# Mux_Demux.net
KiCad netlist of a schematic drawn in Altium Designer
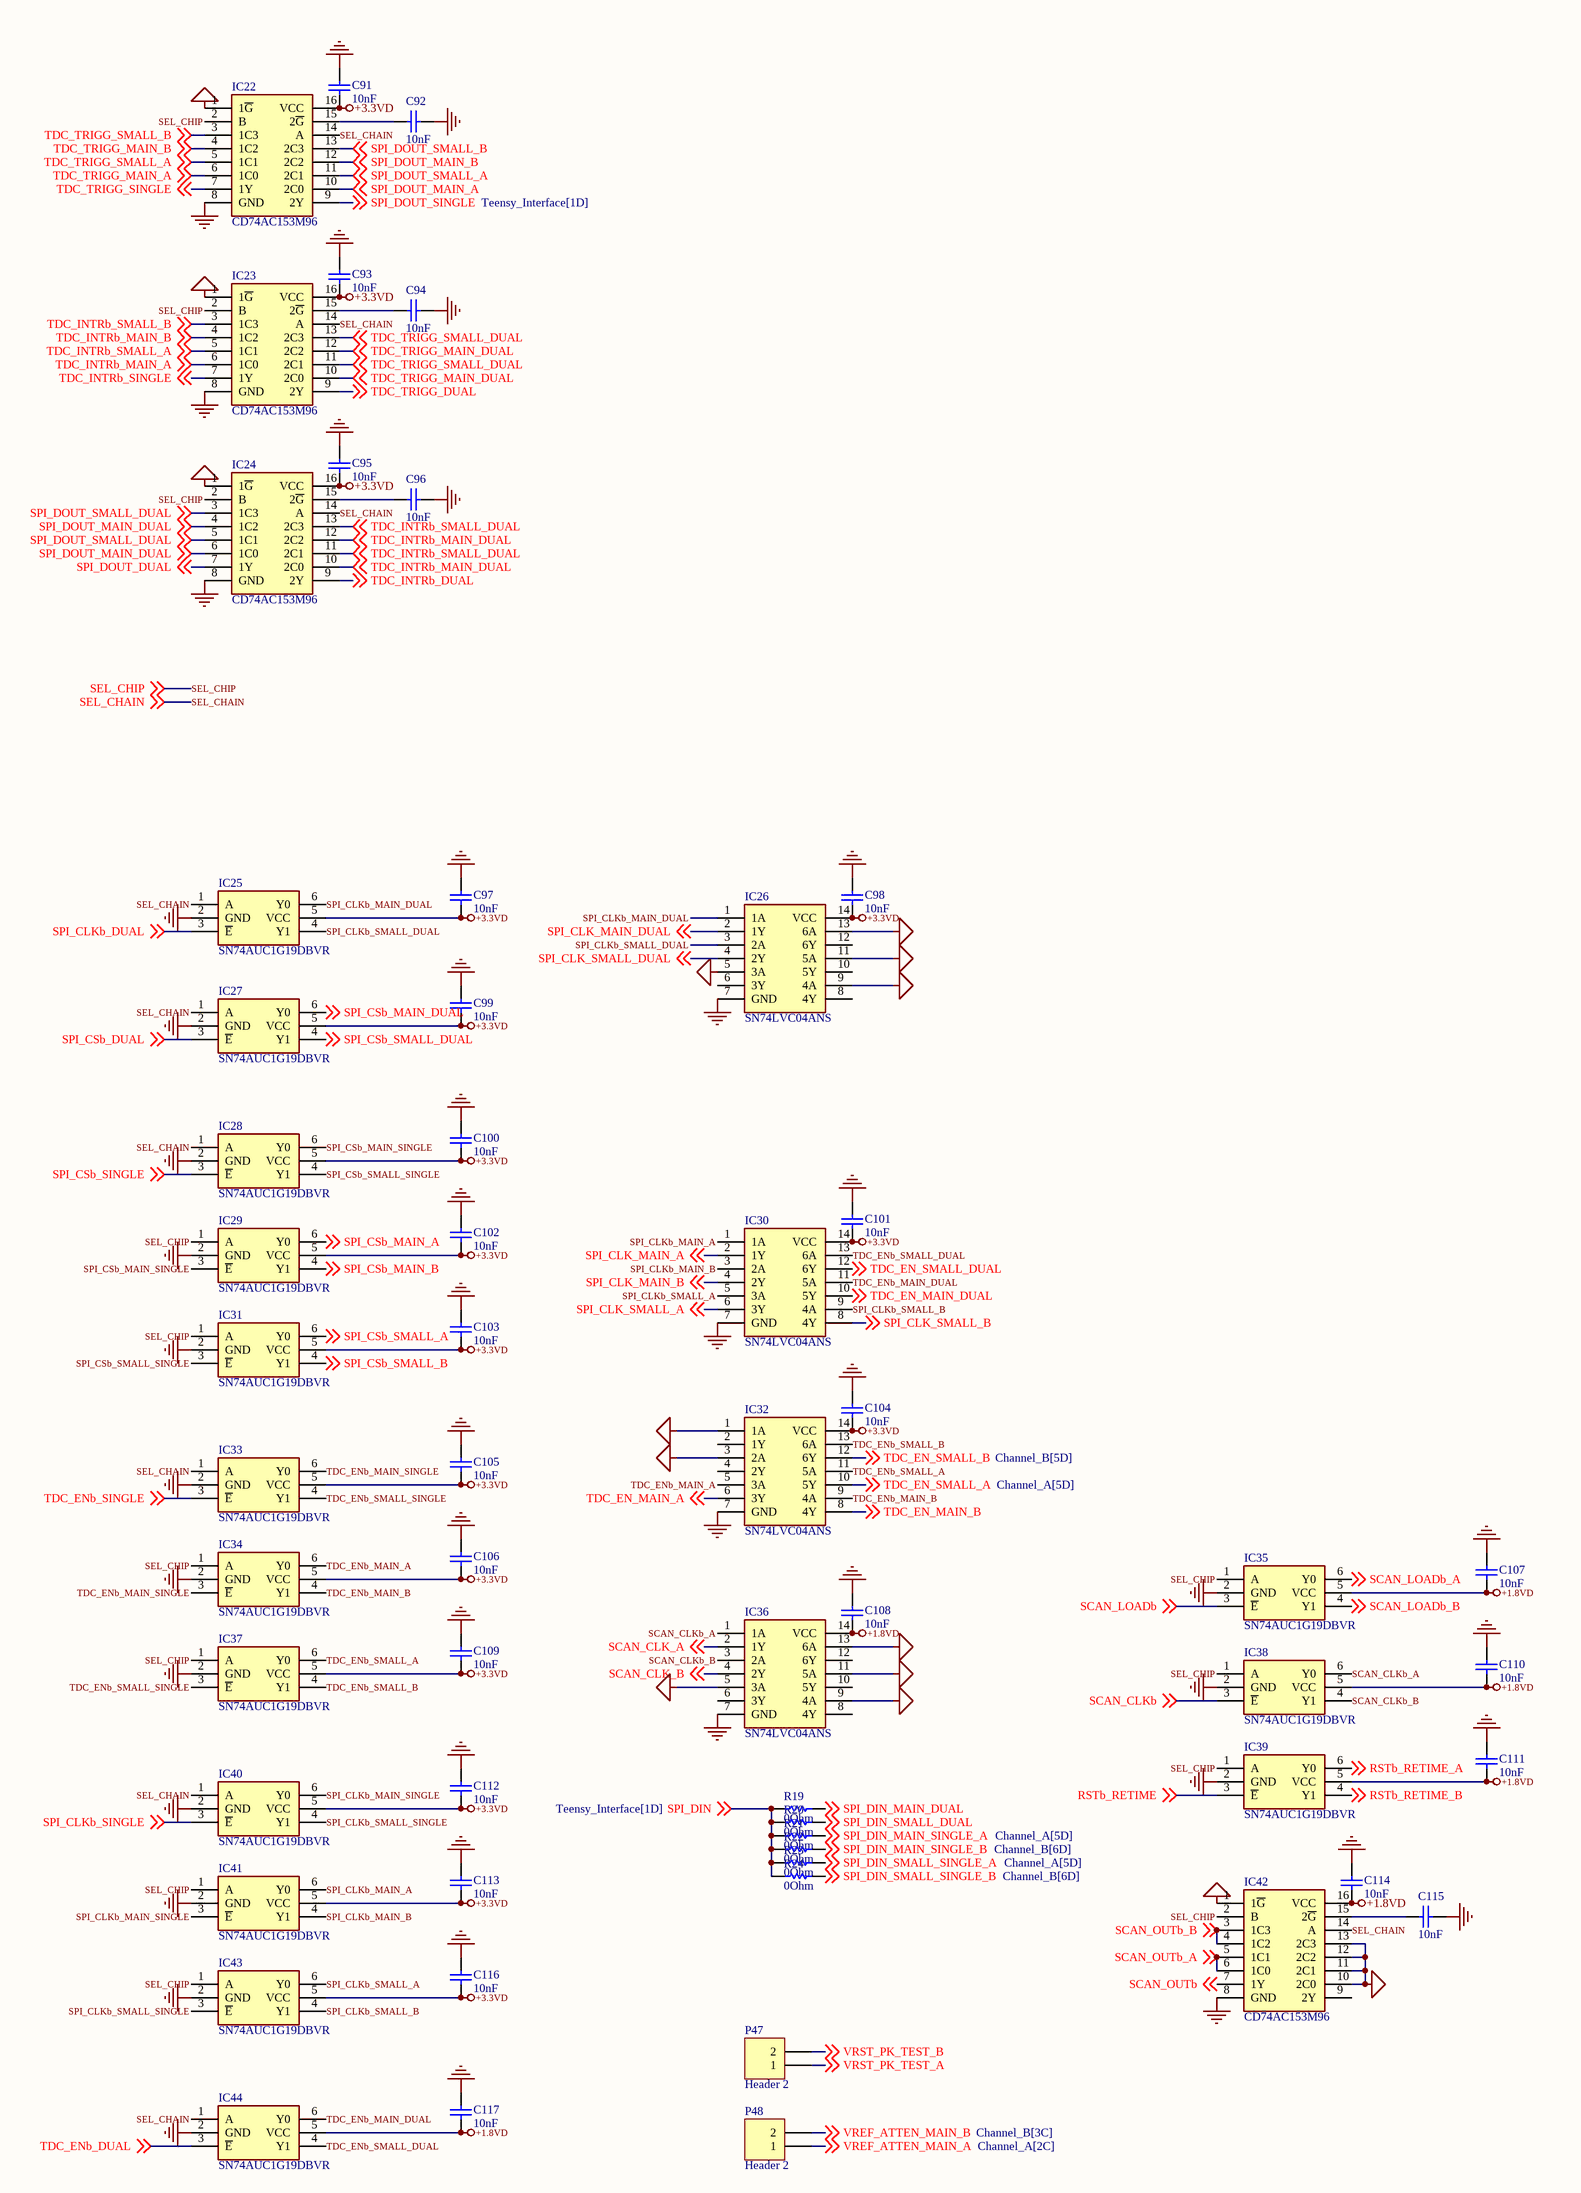
[diagram p0: Mux_Demux.SchDoc]

(export (version "E")
  (design (tool "Eeschema 10.0.6"))
  (components
    (comp (ref "C91")
      (value "10nF")
      (footprint "CAPC1608X90X35ML10T15")
      (description "0603")
      (fields (field (name "MANUFACTURER") "Murata"))
      (libsource (lib "Altium Content Vault") (part "CAP-NP-2"))
    )
    (comp (ref "C92")
      (value "10nF")
      (footprint "CAPC1608X90X35ML10T15")
      (description "0603")
      (fields (field (name "MANUFACTURER") "Murata"))
      (libsource (lib "Altium Content Vault") (part "CAP-NP-2"))
    )
    (comp (ref "C93")
      (value "10nF")
      (footprint "CAPC1608X90X35ML10T15")
      (description "0603")
      (fields (field (name "MANUFACTURER") "Murata"))
      (libsource (lib "Altium Content Vault") (part "CAP-NP-2"))
    )
    (comp (ref "C94")
      (value "10nF")
      (footprint "CAPC1608X90X35ML10T15")
      (description "0603")
      (fields (field (name "MANUFACTURER") "Murata"))
      (libsource (lib "Altium Content Vault") (part "CAP-NP-2"))
    )
    (comp (ref "C95")
      (value "10nF")
      (footprint "CAPC1608X90X35ML10T15")
      (description "0603")
      (fields (field (name "MANUFACTURER") "Murata"))
      (libsource (lib "Altium Content Vault") (part "CAP-NP-2"))
    )
    (comp (ref "C96")
      (value "10nF")
      (footprint "CAPC1608X90X35ML10T15")
      (description "0603")
      (fields (field (name "MANUFACTURER") "Murata"))
      (libsource (lib "Altium Content Vault") (part "CAP-NP-2"))
    )
    (comp (ref "C97")
      (value "10nF")
      (footprint "CAPC1608X90X35ML10T15")
      (description "0603")
      (fields (field (name "MANUFACTURER") "Murata"))
      (libsource (lib "Altium Content Vault") (part "CAP-NP-2"))
    )
    (comp (ref "C98")
      (value "10nF")
      (footprint "CAPC1608X90X35ML10T15")
      (description "0603")
      (fields (field (name "MANUFACTURER") "Murata"))
      (libsource (lib "Altium Content Vault") (part "CAP-NP-2"))
    )
    (comp (ref "C99")
      (value "10nF")
      (footprint "CAPC1608X90X35ML10T15")
      (description "0603")
      (fields (field (name "MANUFACTURER") "Murata"))
      (libsource (lib "Altium Content Vault") (part "CAP-NP-2"))
    )
    (comp (ref "C100")
      (value "10nF")
      (footprint "CAPC1608X90X35ML10T15")
      (description "0603")
      (fields (field (name "MANUFACTURER") "Murata"))
      (libsource (lib "Altium Content Vault") (part "CAP-NP-2"))
    )
    (comp (ref "C101")
      (value "10nF")
      (footprint "CAPC1608X90X35ML10T15")
      (description "0603")
      (fields (field (name "MANUFACTURER") "Murata"))
      (libsource (lib "Altium Content Vault") (part "CAP-NP-2"))
    )
    (comp (ref "C102")
      (value "10nF")
      (footprint "CAPC1608X90X35ML10T15")
      (description "0603")
      (fields (field (name "MANUFACTURER") "Murata"))
      (libsource (lib "Altium Content Vault") (part "CAP-NP-2"))
    )
    (comp (ref "C103")
      (value "10nF")
      (footprint "CAPC1608X90X35ML10T15")
      (description "0603")
      (fields (field (name "MANUFACTURER") "Murata"))
      (libsource (lib "Altium Content Vault") (part "CAP-NP-2"))
    )
    (comp (ref "C104")
      (value "10nF")
      (footprint "CAPC1608X90X35ML10T15")
      (description "0603")
      (fields (field (name "MANUFACTURER") "Murata"))
      (libsource (lib "Altium Content Vault") (part "CAP-NP-2"))
    )
    (comp (ref "C105")
      (value "10nF")
      (footprint "CAPC1608X90X35ML10T15")
      (description "0603")
      (fields (field (name "MANUFACTURER") "Murata"))
      (libsource (lib "Altium Content Vault") (part "CAP-NP-2"))
    )
    (comp (ref "C106")
      (value "10nF")
      (footprint "CAPC1608X90X35ML10T15")
      (description "0603")
      (fields (field (name "MANUFACTURER") "Murata"))
      (libsource (lib "Altium Content Vault") (part "CAP-NP-2"))
    )
    (comp (ref "C107")
      (value "10nF")
      (footprint "CAPC1608X90X35ML10T15")
      (description "0603")
      (fields (field (name "MANUFACTURER") "Murata"))
      (libsource (lib "Altium Content Vault") (part "CAP-NP-2"))
    )
    (comp (ref "C108")
      (value "10nF")
      (footprint "CAPC1608X90X35ML10T15")
      (description "0603")
      (fields (field (name "MANUFACTURER") "Murata"))
      (libsource (lib "Altium Content Vault") (part "CAP-NP-2"))
    )
    (comp (ref "C109")
      (value "10nF")
      (footprint "CAPC1608X90X35ML10T15")
      (description "0603")
      (fields (field (name "MANUFACTURER") "Murata"))
      (libsource (lib "Altium Content Vault") (part "CAP-NP-2"))
    )
    (comp (ref "C110")
      (value "10nF")
      (footprint "CAPC1608X90X35ML10T15")
      (description "0603")
      (fields (field (name "MANUFACTURER") "Murata"))
      (libsource (lib "Altium Content Vault") (part "CAP-NP-2"))
    )
    (comp (ref "C111")
      (value "10nF")
      (footprint "CAPC1608X90X35ML10T15")
      (description "0603")
      (fields (field (name "MANUFACTURER") "Murata"))
      (libsource (lib "Altium Content Vault") (part "CAP-NP-2"))
    )
    (comp (ref "C112")
      (value "10nF")
      (footprint "CAPC1608X90X35ML10T15")
      (description "0603")
      (fields (field (name "MANUFACTURER") "Murata"))
      (libsource (lib "Altium Content Vault") (part "CAP-NP-2"))
    )
    (comp (ref "C113")
      (value "10nF")
      (footprint "CAPC1608X90X35ML10T15")
      (description "0603")
      (fields (field (name "MANUFACTURER") "Murata"))
      (libsource (lib "Altium Content Vault") (part "CAP-NP-2"))
    )
    (comp (ref "C114")
      (value "10nF")
      (footprint "CAPC1608X90X35ML10T15")
      (description "0603")
      (fields (field (name "MANUFACTURER") "Murata"))
      (libsource (lib "Altium Content Vault") (part "CAP-NP-2"))
    )
    (comp (ref "C115")
      (value "10nF")
      (footprint "CAPC1608X90X35ML10T15")
      (description "0603")
      (fields (field (name "MANUFACTURER") "Murata"))
      (libsource (lib "Altium Content Vault") (part "CAP-NP-2"))
    )
    (comp (ref "C116")
      (value "10nF")
      (footprint "CAPC1608X90X35ML10T15")
      (description "0603")
      (fields (field (name "MANUFACTURER") "Murata"))
      (libsource (lib "Altium Content Vault") (part "CAP-NP-2"))
    )
    (comp (ref "C117")
      (value "10nF")
      (footprint "CAPC1608X90X35ML10T15")
      (description "0603")
      (fields (field (name "MANUFACTURER") "Murata"))
      (libsource (lib "Altium Content Vault") (part "CAP-NP-2"))
    )
    (comp (ref "IC22")
      (value "CD74AC153M96")
      (footprint "SamacSys:SOIC127P600X175-16N")
      (description "Encoders, Decoders, Multiplexers & Demultiplexers Dual 4-Input")
      (fields (field (name "MOUSER PART NUMBER") "595-CD74AC153M96"))
      (libsource (lib "*") (part "CD74AC153M96"))
    )
    (comp (ref "IC23")
      (value "CD74AC153M96")
      (footprint "SamacSys:SOIC127P600X175-16N")
      (description "Encoders, Decoders, Multiplexers & Demultiplexers Dual 4-Input")
      (fields (field (name "MOUSER PART NUMBER") "595-CD74AC153M96"))
      (libsource (lib "*") (part "CD74AC153M96"))
    )
    (comp (ref "IC24")
      (value "CD74AC153M96")
      (footprint "SamacSys:SOIC127P600X175-16N")
      (description "Encoders, Decoders, Multiplexers & Demultiplexers Dual 4-Input")
      (fields (field (name "MOUSER PART NUMBER") "595-CD74AC153M96"))
      (libsource (lib "*") (part "CD74AC153M96"))
    )
    (comp (ref "IC25")
      (value "SN74AUC1G19DBVR")
      (footprint "SamacSys:SOT95P280X145-6N")
      (description "Encoders, Decoders, Multiplexers & Demultiplexers 1 of 2 Decoder DeMultxe")
      (fields (field (name "MOUSER PART NUMBER") "595-SN74AUC1G19DBVR"))
      (libsource (lib "*") (part "SN74AUC1G19DBVR"))
    )
    (comp (ref "IC26")
      (value "SN74LVC04ANS")
      (footprint "SamacSys:SOIC127P780X200-14N")
      (description "Inverters Hex Inverter")
      (fields (field (name "MOUSER PART NUMBER") "595-SN74LVC04ANS"))
      (libsource (lib "*") (part "SN74LVC04ANS"))
    )
    (comp (ref "IC27")
      (value "SN74AUC1G19DBVR")
      (footprint "SamacSys:SOT95P280X145-6N")
      (description "Encoders, Decoders, Multiplexers & Demultiplexers 1 of 2 Decoder DeMultxe")
      (fields (field (name "MOUSER PART NUMBER") "595-SN74AUC1G19DBVR"))
      (libsource (lib "*") (part "SN74AUC1G19DBVR"))
    )
    (comp (ref "IC28")
      (value "SN74AUC1G19DBVR")
      (footprint "SamacSys:SOT95P280X145-6N")
      (description "Encoders, Decoders, Multiplexers & Demultiplexers 1 of 2 Decoder DeMultxe")
      (fields (field (name "MOUSER PART NUMBER") "595-SN74AUC1G19DBVR"))
      (libsource (lib "*") (part "SN74AUC1G19DBVR"))
    )
    (comp (ref "IC29")
      (value "SN74AUC1G19DBVR")
      (footprint "SamacSys:SOT95P280X145-6N")
      (description "Encoders, Decoders, Multiplexers & Demultiplexers 1 of 2 Decoder DeMultxe")
      (fields (field (name "MOUSER PART NUMBER") "595-SN74AUC1G19DBVR"))
      (libsource (lib "*") (part "SN74AUC1G19DBVR"))
    )
    (comp (ref "IC30")
      (value "SN74LVC04ANS")
      (footprint "SamacSys:SOIC127P780X200-14N")
      (description "Inverters Hex Inverter")
      (fields (field (name "MOUSER PART NUMBER") "595-SN74LVC04ANS"))
      (libsource (lib "*") (part "SN74LVC04ANS"))
    )
    (comp (ref "IC31")
      (value "SN74AUC1G19DBVR")
      (footprint "SamacSys:SOT95P280X145-6N")
      (description "Encoders, Decoders, Multiplexers & Demultiplexers 1 of 2 Decoder DeMultxe")
      (fields (field (name "MOUSER PART NUMBER") "595-SN74AUC1G19DBVR"))
      (libsource (lib "*") (part "SN74AUC1G19DBVR"))
    )
    (comp (ref "IC32")
      (value "SN74LVC04ANS")
      (footprint "SamacSys:SOIC127P780X200-14N")
      (description "Inverters Hex Inverter")
      (fields (field (name "MOUSER PART NUMBER") "595-SN74LVC04ANS"))
      (libsource (lib "*") (part "SN74LVC04ANS"))
    )
    (comp (ref "IC33")
      (value "SN74AUC1G19DBVR")
      (footprint "SamacSys:SOT95P280X145-6N")
      (description "Encoders, Decoders, Multiplexers & Demultiplexers 1 of 2 Decoder DeMultxe")
      (fields (field (name "MOUSER PART NUMBER") "595-SN74AUC1G19DBVR"))
      (libsource (lib "*") (part "SN74AUC1G19DBVR"))
    )
    (comp (ref "IC34")
      (value "SN74AUC1G19DBVR")
      (footprint "SamacSys:SOT95P280X145-6N")
      (description "Encoders, Decoders, Multiplexers & Demultiplexers 1 of 2 Decoder DeMultxe")
      (fields (field (name "MOUSER PART NUMBER") "595-SN74AUC1G19DBVR"))
      (libsource (lib "*") (part "SN74AUC1G19DBVR"))
    )
    (comp (ref "IC35")
      (value "SN74AUC1G19DBVR")
      (footprint "SamacSys:SOT95P280X145-6N")
      (description "Encoders, Decoders, Multiplexers & Demultiplexers 1 of 2 Decoder DeMultxe")
      (fields (field (name "MOUSER PART NUMBER") "595-SN74AUC1G19DBVR"))
      (libsource (lib "*") (part "SN74AUC1G19DBVR"))
    )
    (comp (ref "IC36")
      (value "SN74LVC04ANS")
      (footprint "SamacSys:SOIC127P780X200-14N")
      (description "Inverters Hex Inverter")
      (fields (field (name "MOUSER PART NUMBER") "595-SN74LVC04ANS"))
      (libsource (lib "*") (part "SN74LVC04ANS"))
    )
    (comp (ref "IC37")
      (value "SN74AUC1G19DBVR")
      (footprint "SamacSys:SOT95P280X145-6N")
      (description "Encoders, Decoders, Multiplexers & Demultiplexers 1 of 2 Decoder DeMultxe")
      (fields (field (name "MOUSER PART NUMBER") "595-SN74AUC1G19DBVR"))
      (libsource (lib "*") (part "SN74AUC1G19DBVR"))
    )
    (comp (ref "IC38")
      (value "SN74AUC1G19DBVR")
      (footprint "SamacSys:SOT95P280X145-6N")
      (description "Encoders, Decoders, Multiplexers & Demultiplexers 1 of 2 Decoder DeMultxe")
      (fields (field (name "MOUSER PART NUMBER") "595-SN74AUC1G19DBVR"))
      (libsource (lib "*") (part "SN74AUC1G19DBVR"))
    )
    (comp (ref "IC39")
      (value "SN74AUC1G19DBVR")
      (footprint "SamacSys:SOT95P280X145-6N")
      (description "Encoders, Decoders, Multiplexers & Demultiplexers 1 of 2 Decoder DeMultxe")
      (fields (field (name "MOUSER PART NUMBER") "595-SN74AUC1G19DBVR"))
      (libsource (lib "*") (part "SN74AUC1G19DBVR"))
    )
    (comp (ref "IC40")
      (value "SN74AUC1G19DBVR")
      (footprint "SamacSys:SOT95P280X145-6N")
      (description "Encoders, Decoders, Multiplexers & Demultiplexers 1 of 2 Decoder DeMultxe")
      (fields (field (name "MOUSER PART NUMBER") "595-SN74AUC1G19DBVR"))
      (libsource (lib "*") (part "SN74AUC1G19DBVR"))
    )
    (comp (ref "IC41")
      (value "SN74AUC1G19DBVR")
      (footprint "SamacSys:SOT95P280X145-6N")
      (description "Encoders, Decoders, Multiplexers & Demultiplexers 1 of 2 Decoder DeMultxe")
      (fields (field (name "MOUSER PART NUMBER") "595-SN74AUC1G19DBVR"))
      (libsource (lib "*") (part "SN74AUC1G19DBVR"))
    )
    (comp (ref "IC42")
      (value "CD74AC153M96")
      (footprint "SamacSys:SOIC127P600X175-16N")
      (description "Encoders, Decoders, Multiplexers & Demultiplexers Dual 4-Input")
      (fields (field (name "MOUSER PART NUMBER") "595-CD74AC153M96"))
      (libsource (lib "*") (part "CD74AC153M96"))
    )
    (comp (ref "IC43")
      (value "SN74AUC1G19DBVR")
      (footprint "SamacSys:SOT95P280X145-6N")
      (description "Encoders, Decoders, Multiplexers & Demultiplexers 1 of 2 Decoder DeMultxe")
      (fields (field (name "MOUSER PART NUMBER") "595-SN74AUC1G19DBVR"))
      (libsource (lib "*") (part "SN74AUC1G19DBVR"))
    )
    (comp (ref "IC44")
      (value "SN74AUC1G19DBVR")
      (footprint "SamacSys:SOT95P280X145-6N")
      (description "Encoders, Decoders, Multiplexers & Demultiplexers 1 of 2 Decoder DeMultxe")
      (fields (field (name "MOUSER PART NUMBER") "595-SN74AUC1G19DBVR"))
      (libsource (lib "*") (part "SN74AUC1G19DBVR"))
    )
    (comp (ref "P47")
      (value "Header 2")
      (footprint "HDR1X2")
      (description "Header, 2-Pin")
      (fields (field (name "PUBLISHER") "Altium Limited"))
      (libsource (lib "Miscellaneous Connectors") (part "Header 2"))
    )
    (comp (ref "P48")
      (value "Header 2")
      (footprint "HDR1X2")
      (description "Header, 2-Pin")
      (fields (field (name "PUBLISHER") "Altium Limited"))
      (libsource (lib "Miscellaneous Connectors") (part "Header 2"))
    )
    (comp (ref "R19")
      (value "0Ohm")
      (footprint "RESC1609X50X30NL8T20")
      (description "0603")
      (fields (field (name "MANUFACTURER") "Vishay Semiconductor"))
      (libsource (lib "Altium Content Vault") (part "RES-2"))
    )
    (comp (ref "R20")
      (value "0Ohm")
      (footprint "RESC1609X50X30NL8T20")
      (description "0603")
      (fields (field (name "MANUFACTURER") "Vishay Semiconductor"))
      (libsource (lib "Altium Content Vault") (part "RES-2"))
    )
    (comp (ref "R21")
      (value "0Ohm")
      (footprint "RESC1609X50X30NL8T20")
      (description "0603")
      (fields (field (name "MANUFACTURER") "Vishay Semiconductor"))
      (libsource (lib "Altium Content Vault") (part "RES-2"))
    )
    (comp (ref "R22")
      (value "0Ohm")
      (footprint "RESC1609X50X30NL8T20")
      (description "0603")
      (fields (field (name "MANUFACTURER") "Vishay Semiconductor"))
      (libsource (lib "Altium Content Vault") (part "RES-2"))
    )
    (comp (ref "R23")
      (value "0Ohm")
      (footprint "RESC1609X50X30NL8T20")
      (description "0603")
      (fields (field (name "MANUFACTURER") "Vishay Semiconductor"))
      (libsource (lib "Altium Content Vault") (part "RES-2"))
    )
    (comp (ref "R24")
      (value "0Ohm")
      (footprint "RESC1609X50X30NL8T20")
      (description "0603")
      (fields (field (name "MANUFACTURER") "Vishay Semiconductor"))
      (libsource (lib "Altium Content Vault") (part "RES-2"))
    )
  )
  (nets
    (net (code "1") (name "+1.8VD") (class "Default")
      (node (ref "C107") (pin "1") (pinfunction "1_1") (pintype "passive"))
      (node (ref "C108") (pin "1") (pinfunction "1_1") (pintype "passive"))
      (node (ref "C110") (pin "1") (pinfunction "1_1") (pintype "passive"))
      (node (ref "C111") (pin "1") (pinfunction "1_1") (pintype "passive"))
      (node (ref "C114") (pin "1") (pinfunction "1_1") (pintype "passive"))
      (node (ref "C117") (pin "1") (pinfunction "1_1") (pintype "passive"))
      (node (ref "IC35") (pin "5") (pinfunction "VCC_5") (pintype "passive"))
      (node (ref "IC36") (pin "14") (pinfunction "VCC_14") (pintype "passive"))
      (node (ref "IC38") (pin "5") (pinfunction "VCC_5") (pintype "passive"))
      (node (ref "IC39") (pin "5") (pinfunction "VCC_5") (pintype "passive"))
      (node (ref "IC42") (pin "16") (pinfunction "VCC_16") (pintype "passive"))
      (node (ref "IC44") (pin "5") (pinfunction "VCC_5") (pintype "passive"))
    )
    (net (code "2") (name "+3.3VD") (class "Default")
      (node (ref "C100") (pin "1") (pinfunction "1_1") (pintype "passive"))
      (node (ref "C101") (pin "1") (pinfunction "1_1") (pintype "passive"))
      (node (ref "C102") (pin "1") (pinfunction "1_1") (pintype "passive"))
      (node (ref "C103") (pin "1") (pinfunction "1_1") (pintype "passive"))
      (node (ref "C104") (pin "1") (pinfunction "1_1") (pintype "passive"))
      (node (ref "C105") (pin "1") (pinfunction "1_1") (pintype "passive"))
      (node (ref "C106") (pin "1") (pinfunction "1_1") (pintype "passive"))
      (node (ref "C109") (pin "1") (pinfunction "1_1") (pintype "passive"))
      (node (ref "C112") (pin "1") (pinfunction "1_1") (pintype "passive"))
      (node (ref "C113") (pin "1") (pinfunction "1_1") (pintype "passive"))
      (node (ref "C116") (pin "1") (pinfunction "1_1") (pintype "passive"))
      (node (ref "C91") (pin "1") (pinfunction "1_1") (pintype "passive"))
      (node (ref "C93") (pin "1") (pinfunction "1_1") (pintype "passive"))
      (node (ref "C95") (pin "1") (pinfunction "1_1") (pintype "passive"))
      (node (ref "C97") (pin "1") (pinfunction "1_1") (pintype "passive"))
      (node (ref "C98") (pin "1") (pinfunction "1_1") (pintype "passive"))
      (node (ref "C99") (pin "1") (pinfunction "1_1") (pintype "passive"))
      (node (ref "IC22") (pin "16") (pinfunction "VCC_16") (pintype "passive"))
      (node (ref "IC23") (pin "16") (pinfunction "VCC_16") (pintype "passive"))
      (node (ref "IC24") (pin "16") (pinfunction "VCC_16") (pintype "passive"))
      (node (ref "IC25") (pin "5") (pinfunction "VCC_5") (pintype "passive"))
      (node (ref "IC26") (pin "14") (pinfunction "VCC_14") (pintype "passive"))
      (node (ref "IC27") (pin "5") (pinfunction "VCC_5") (pintype "passive"))
      (node (ref "IC28") (pin "5") (pinfunction "VCC_5") (pintype "passive"))
      (node (ref "IC29") (pin "5") (pinfunction "VCC_5") (pintype "passive"))
      (node (ref "IC30") (pin "14") (pinfunction "VCC_14") (pintype "passive"))
      (node (ref "IC31") (pin "5") (pinfunction "VCC_5") (pintype "passive"))
      (node (ref "IC32") (pin "14") (pinfunction "VCC_14") (pintype "passive"))
      (node (ref "IC33") (pin "5") (pinfunction "VCC_5") (pintype "passive"))
      (node (ref "IC34") (pin "5") (pinfunction "VCC_5") (pintype "passive"))
      (node (ref "IC37") (pin "5") (pinfunction "VCC_5") (pintype "passive"))
      (node (ref "IC40") (pin "5") (pinfunction "VCC_5") (pintype "passive"))
      (node (ref "IC41") (pin "5") (pinfunction "VCC_5") (pintype "passive"))
      (node (ref "IC43") (pin "5") (pinfunction "VCC_5") (pintype "passive"))
    )
    (net (code "3") (name "/SCAN_CLKb_A") (class "Default")
      (node (ref "IC36") (pin "1") (pinfunction "1A_1") (pintype "passive"))
      (node (ref "IC38") (pin "6") (pinfunction "Y0_6") (pintype "passive"))
    )
    (net (code "4") (name "/SCAN_CLKb_B") (class "Default")
      (node (ref "IC36") (pin "3") (pinfunction "2A_3") (pintype "passive"))
      (node (ref "IC38") (pin "4") (pinfunction "Y1_4") (pintype "passive"))
    )
    (net (code "5") (name "/SPI_CLKb_MAIN_A") (class "Default")
      (node (ref "IC30") (pin "1") (pinfunction "1A_1") (pintype "passive"))
      (node (ref "IC41") (pin "6") (pinfunction "Y0_6") (pintype "passive"))
    )
    (net (code "6") (name "/SPI_CLKb_MAIN_B") (class "Default")
      (node (ref "IC30") (pin "3") (pinfunction "2A_3") (pintype "passive"))
      (node (ref "IC41") (pin "4") (pinfunction "Y1_4") (pintype "passive"))
    )
    (net (code "7") (name "/SPI_CLKb_MAIN_DUAL") (class "Default")
      (node (ref "IC25") (pin "6") (pinfunction "Y0_6") (pintype "passive"))
      (node (ref "IC26") (pin "1") (pinfunction "1A_1") (pintype "passive"))
    )
    (net (code "8") (name "/SPI_CLKb_MAIN_SINGLE") (class "Default")
      (node (ref "IC40") (pin "6") (pinfunction "Y0_6") (pintype "passive"))
      (node (ref "IC41") (pin "3") (pinfunction "~{E}_3") (pintype "passive"))
    )
    (net (code "9") (name "/SPI_CLKb_SMALL_A") (class "Default")
      (node (ref "IC30") (pin "5") (pinfunction "3A_5") (pintype "passive"))
      (node (ref "IC43") (pin "6") (pinfunction "Y0_6") (pintype "passive"))
    )
    (net (code "10") (name "/SPI_CLKb_SMALL_B") (class "Default")
      (node (ref "IC30") (pin "9") (pinfunction "4A_9") (pintype "passive"))
      (node (ref "IC43") (pin "4") (pinfunction "Y1_4") (pintype "passive"))
    )
    (net (code "11") (name "/SPI_CLKb_SMALL_DUAL") (class "Default")
      (node (ref "IC25") (pin "4") (pinfunction "Y1_4") (pintype "passive"))
      (node (ref "IC26") (pin "3") (pinfunction "2A_3") (pintype "passive"))
    )
    (net (code "12") (name "/SPI_CLKb_SMALL_SINGLE") (class "Default")
      (node (ref "IC40") (pin "4") (pinfunction "Y1_4") (pintype "passive"))
      (node (ref "IC43") (pin "3") (pinfunction "~{E}_3") (pintype "passive"))
    )
    (net (code "13") (name "/SPI_CSb_MAIN_SINGLE") (class "Default")
      (node (ref "IC28") (pin "6") (pinfunction "Y0_6") (pintype "passive"))
      (node (ref "IC29") (pin "3") (pinfunction "~{E}_3") (pintype "passive"))
    )
    (net (code "14") (name "/SPI_CSb_SMALL_SINGLE") (class "Default")
      (node (ref "IC28") (pin "4") (pinfunction "Y1_4") (pintype "passive"))
      (node (ref "IC31") (pin "3") (pinfunction "~{E}_3") (pintype "passive"))
    )
    (net (code "15") (name "/TDC_ENb_MAIN_A") (class "Default")
      (node (ref "IC32") (pin "5") (pinfunction "3A_5") (pintype "passive"))
      (node (ref "IC34") (pin "6") (pinfunction "Y0_6") (pintype "passive"))
    )
    (net (code "16") (name "/TDC_ENb_MAIN_B") (class "Default")
      (node (ref "IC32") (pin "9") (pinfunction "4A_9") (pintype "passive"))
      (node (ref "IC34") (pin "4") (pinfunction "Y1_4") (pintype "passive"))
    )
    (net (code "17") (name "/TDC_ENb_MAIN_DUAL") (class "Default")
      (node (ref "IC30") (pin "11") (pinfunction "5A_11") (pintype "passive"))
      (node (ref "IC44") (pin "6") (pinfunction "Y0_6") (pintype "passive"))
    )
    (net (code "18") (name "/TDC_ENb_MAIN_SINGLE") (class "Default")
      (node (ref "IC33") (pin "6") (pinfunction "Y0_6") (pintype "passive"))
      (node (ref "IC34") (pin "3") (pinfunction "~{E}_3") (pintype "passive"))
    )
    (net (code "19") (name "/TDC_ENb_SMALL_A") (class "Default")
      (node (ref "IC32") (pin "11") (pinfunction "5A_11") (pintype "passive"))
      (node (ref "IC37") (pin "6") (pinfunction "Y0_6") (pintype "passive"))
    )
    (net (code "20") (name "/TDC_ENb_SMALL_B") (class "Default")
      (node (ref "IC32") (pin "13") (pinfunction "6A_13") (pintype "passive"))
      (node (ref "IC37") (pin "4") (pinfunction "Y1_4") (pintype "passive"))
    )
    (net (code "21") (name "/TDC_ENb_SMALL_DUAL") (class "Default")
      (node (ref "IC30") (pin "13") (pinfunction "6A_13") (pintype "passive"))
      (node (ref "IC44") (pin "4") (pinfunction "Y1_4") (pintype "passive"))
    )
    (net (code "22") (name "/TDC_ENb_SMALL_SINGLE") (class "Default")
      (node (ref "IC33") (pin "4") (pinfunction "Y1_4") (pintype "passive"))
      (node (ref "IC37") (pin "3") (pinfunction "~{E}_3") (pintype "passive"))
    )
    (net (code "23") (name "GND") (class "Default")
      (node (ref "C100") (pin "2") (pinfunction "2_2") (pintype "passive"))
      (node (ref "C101") (pin "2") (pinfunction "2_2") (pintype "passive"))
      (node (ref "C102") (pin "2") (pinfunction "2_2") (pintype "passive"))
      (node (ref "C103") (pin "2") (pinfunction "2_2") (pintype "passive"))
      (node (ref "C104") (pin "2") (pinfunction "2_2") (pintype "passive"))
      (node (ref "C105") (pin "2") (pinfunction "2_2") (pintype "passive"))
      (node (ref "C106") (pin "2") (pinfunction "2_2") (pintype "passive"))
      (node (ref "C107") (pin "2") (pinfunction "2_2") (pintype "passive"))
      (node (ref "C108") (pin "2") (pinfunction "2_2") (pintype "passive"))
      (node (ref "C109") (pin "2") (pinfunction "2_2") (pintype "passive"))
      (node (ref "C110") (pin "2") (pinfunction "2_2") (pintype "passive"))
      (node (ref "C111") (pin "2") (pinfunction "2_2") (pintype "passive"))
      (node (ref "C112") (pin "2") (pinfunction "2_2") (pintype "passive"))
      (node (ref "C113") (pin "2") (pinfunction "2_2") (pintype "passive"))
      (node (ref "C114") (pin "2") (pinfunction "2_2") (pintype "passive"))
      (node (ref "C115") (pin "2") (pinfunction "2_2") (pintype "passive"))
      (node (ref "C116") (pin "2") (pinfunction "2_2") (pintype "passive"))
      (node (ref "C117") (pin "2") (pinfunction "2_2") (pintype "passive"))
      (node (ref "C91") (pin "2") (pinfunction "2_2") (pintype "passive"))
      (node (ref "C92") (pin "2") (pinfunction "2_2") (pintype "passive"))
      (node (ref "C93") (pin "2") (pinfunction "2_2") (pintype "passive"))
      (node (ref "C94") (pin "2") (pinfunction "2_2") (pintype "passive"))
      (node (ref "C95") (pin "2") (pinfunction "2_2") (pintype "passive"))
      (node (ref "C96") (pin "2") (pinfunction "2_2") (pintype "passive"))
      (node (ref "C97") (pin "2") (pinfunction "2_2") (pintype "passive"))
      (node (ref "C98") (pin "2") (pinfunction "2_2") (pintype "passive"))
      (node (ref "C99") (pin "2") (pinfunction "2_2") (pintype "passive"))
      (node (ref "IC22") (pin "1") (pinfunction "1~{G}_1") (pintype "passive"))
      (node (ref "IC22") (pin "8") (pinfunction "GND_8") (pintype "passive"))
      (node (ref "IC23") (pin "1") (pinfunction "1~{G}_1") (pintype "passive"))
      (node (ref "IC23") (pin "8") (pinfunction "GND_8") (pintype "passive"))
      (node (ref "IC24") (pin "1") (pinfunction "1~{G}_1") (pintype "passive"))
      (node (ref "IC24") (pin "8") (pinfunction "GND_8") (pintype "passive"))
      (node (ref "IC25") (pin "2") (pinfunction "GND_2") (pintype "passive"))
      (node (ref "IC26") (pin "11") (pinfunction "5A_11") (pintype "passive"))
      (node (ref "IC26") (pin "13") (pinfunction "6A_13") (pintype "passive"))
      (node (ref "IC26") (pin "5") (pinfunction "3A_5") (pintype "passive"))
      (node (ref "IC26") (pin "7") (pinfunction "GND_7") (pintype "passive"))
      (node (ref "IC26") (pin "9") (pinfunction "4A_9") (pintype "passive"))
      (node (ref "IC27") (pin "2") (pinfunction "GND_2") (pintype "passive"))
      (node (ref "IC28") (pin "2") (pinfunction "GND_2") (pintype "passive"))
      (node (ref "IC29") (pin "2") (pinfunction "GND_2") (pintype "passive"))
      (node (ref "IC30") (pin "7") (pinfunction "GND_7") (pintype "passive"))
      (node (ref "IC31") (pin "2") (pinfunction "GND_2") (pintype "passive"))
      (node (ref "IC32") (pin "1") (pinfunction "1A_1") (pintype "passive"))
      (node (ref "IC32") (pin "3") (pinfunction "2A_3") (pintype "passive"))
      (node (ref "IC32") (pin "7") (pinfunction "GND_7") (pintype "passive"))
      (node (ref "IC33") (pin "2") (pinfunction "GND_2") (pintype "passive"))
      (node (ref "IC34") (pin "2") (pinfunction "GND_2") (pintype "passive"))
      (node (ref "IC35") (pin "2") (pinfunction "GND_2") (pintype "passive"))
      (node (ref "IC36") (pin "11") (pinfunction "5A_11") (pintype "passive"))
      (node (ref "IC36") (pin "13") (pinfunction "6A_13") (pintype "passive"))
      (node (ref "IC36") (pin "5") (pinfunction "3A_5") (pintype "passive"))
      (node (ref "IC36") (pin "7") (pinfunction "GND_7") (pintype "passive"))
      (node (ref "IC36") (pin "9") (pinfunction "4A_9") (pintype "passive"))
      (node (ref "IC37") (pin "2") (pinfunction "GND_2") (pintype "passive"))
      (node (ref "IC38") (pin "2") (pinfunction "GND_2") (pintype "passive"))
      (node (ref "IC39") (pin "2") (pinfunction "GND_2") (pintype "passive"))
      (node (ref "IC40") (pin "2") (pinfunction "GND_2") (pintype "passive"))
      (node (ref "IC41") (pin "2") (pinfunction "GND_2") (pintype "passive"))
      (node (ref "IC42") (pin "1") (pinfunction "1~{G}_1") (pintype "passive"))
      (node (ref "IC42") (pin "10") (pinfunction "2C0_10") (pintype "passive"))
      (node (ref "IC42") (pin "11") (pinfunction "2C1_11") (pintype "passive"))
      (node (ref "IC42") (pin "12") (pinfunction "2C2_12") (pintype "passive"))
      (node (ref "IC42") (pin "13") (pinfunction "2C3_13") (pintype "passive"))
      (node (ref "IC42") (pin "8") (pinfunction "GND_8") (pintype "passive"))
      (node (ref "IC43") (pin "2") (pinfunction "GND_2") (pintype "passive"))
      (node (ref "IC44") (pin "2") (pinfunction "GND_2") (pintype "passive"))
    )
    (net (code "24") (name "Net-(IC22-2~{G})") (class "Default")
      (node (ref "C92") (pin "1") (pinfunction "1_1") (pintype "passive"))
      (node (ref "IC22") (pin "15") (pinfunction "2~{G}_15") (pintype "passive"))
    )
    (net (code "25") (name "Net-(IC23-2~{G})") (class "Default")
      (node (ref "C94") (pin "1") (pinfunction "1_1") (pintype "passive"))
      (node (ref "IC23") (pin "15") (pinfunction "2~{G}_15") (pintype "passive"))
    )
    (net (code "26") (name "Net-(IC24-2~{G})") (class "Default")
      (node (ref "C96") (pin "1") (pinfunction "1_1") (pintype "passive"))
      (node (ref "IC24") (pin "15") (pinfunction "2~{G}_15") (pintype "passive"))
    )
    (net (code "27") (name "Net-(IC42-2~{G})") (class "Default")
      (node (ref "C115") (pin "1") (pinfunction "1_1") (pintype "passive"))
      (node (ref "IC42") (pin "15") (pinfunction "2~{G}_15") (pintype "passive"))
    )
    (net (code "28") (name "RSTb_RETIME") (class "Default")
      (node (ref "IC39") (pin "3") (pinfunction "~{E}_3") (pintype "passive"))
    )
    (net (code "29") (name "RSTb_RETIME_A") (class "Default")
      (node (ref "IC39") (pin "6") (pinfunction "Y0_6") (pintype "passive"))
    )
    (net (code "30") (name "RSTb_RETIME_B") (class "Default")
      (node (ref "IC39") (pin "4") (pinfunction "Y1_4") (pintype "passive"))
    )
    (net (code "31") (name "SCAN_CLK_A") (class "Default")
      (node (ref "IC36") (pin "2") (pinfunction "1Y_2") (pintype "passive"))
    )
    (net (code "32") (name "SCAN_CLK_B") (class "Default")
      (node (ref "IC36") (pin "4") (pinfunction "2Y_4") (pintype "passive"))
    )
    (net (code "33") (name "SCAN_CLKb") (class "Default")
      (node (ref "IC38") (pin "3") (pinfunction "~{E}_3") (pintype "passive"))
    )
    (net (code "34") (name "SCAN_LOADb") (class "Default")
      (node (ref "IC35") (pin "3") (pinfunction "~{E}_3") (pintype "passive"))
    )
    (net (code "35") (name "SCAN_LOADb_A") (class "Default")
      (node (ref "IC35") (pin "6") (pinfunction "Y0_6") (pintype "passive"))
    )
    (net (code "36") (name "SCAN_LOADb_B") (class "Default")
      (node (ref "IC35") (pin "4") (pinfunction "Y1_4") (pintype "passive"))
    )
    (net (code "37") (name "SCAN_OUTb") (class "Default")
      (node (ref "IC42") (pin "7") (pinfunction "1Y_7") (pintype "passive"))
    )
    (net (code "38") (name "SCAN_OUTb_A") (class "Default")
      (node (ref "IC42") (pin "5") (pinfunction "1C1_5") (pintype "passive"))
      (node (ref "IC42") (pin "6") (pinfunction "1C0_6") (pintype "passive"))
    )
    (net (code "39") (name "SCAN_OUTb_B") (class "Default")
      (node (ref "IC42") (pin "3") (pinfunction "1C3_3") (pintype "passive"))
      (node (ref "IC42") (pin "4") (pinfunction "1C2_4") (pintype "passive"))
    )
    (net (code "40") (name "SEL_CHAIN") (class "Default")
      (node (ref "IC22") (pin "14") (pinfunction "A_14") (pintype "passive"))
      (node (ref "IC23") (pin "14") (pinfunction "A_14") (pintype "passive"))
      (node (ref "IC24") (pin "14") (pinfunction "A_14") (pintype "passive"))
      (node (ref "IC25") (pin "1") (pinfunction "A_1") (pintype "passive"))
      (node (ref "IC27") (pin "1") (pinfunction "A_1") (pintype "passive"))
      (node (ref "IC28") (pin "1") (pinfunction "A_1") (pintype "passive"))
      (node (ref "IC33") (pin "1") (pinfunction "A_1") (pintype "passive"))
      (node (ref "IC40") (pin "1") (pinfunction "A_1") (pintype "passive"))
      (node (ref "IC42") (pin "14") (pinfunction "A_14") (pintype "passive"))
      (node (ref "IC44") (pin "1") (pinfunction "A_1") (pintype "passive"))
    )
    (net (code "41") (name "SEL_CHIP") (class "Default")
      (node (ref "IC22") (pin "2") (pinfunction "B_2") (pintype "passive"))
      (node (ref "IC23") (pin "2") (pinfunction "B_2") (pintype "passive"))
      (node (ref "IC24") (pin "2") (pinfunction "B_2") (pintype "passive"))
      (node (ref "IC29") (pin "1") (pinfunction "A_1") (pintype "passive"))
      (node (ref "IC31") (pin "1") (pinfunction "A_1") (pintype "passive"))
      (node (ref "IC34") (pin "1") (pinfunction "A_1") (pintype "passive"))
      (node (ref "IC35") (pin "1") (pinfunction "A_1") (pintype "passive"))
      (node (ref "IC37") (pin "1") (pinfunction "A_1") (pintype "passive"))
      (node (ref "IC38") (pin "1") (pinfunction "A_1") (pintype "passive"))
      (node (ref "IC39") (pin "1") (pinfunction "A_1") (pintype "passive"))
      (node (ref "IC41") (pin "1") (pinfunction "A_1") (pintype "passive"))
      (node (ref "IC42") (pin "2") (pinfunction "B_2") (pintype "passive"))
      (node (ref "IC43") (pin "1") (pinfunction "A_1") (pintype "passive"))
    )
    (net (code "42") (name "SPI_CLK_MAIN_A") (class "Default")
      (node (ref "IC30") (pin "2") (pinfunction "1Y_2") (pintype "passive"))
    )
    (net (code "43") (name "SPI_CLK_MAIN_B") (class "Default")
      (node (ref "IC30") (pin "4") (pinfunction "2Y_4") (pintype "passive"))
    )
    (net (code "44") (name "SPI_CLK_MAIN_DUAL") (class "Default")
      (node (ref "IC26") (pin "2") (pinfunction "1Y_2") (pintype "passive"))
    )
    (net (code "45") (name "SPI_CLK_SMALL_A") (class "Default")
      (node (ref "IC30") (pin "6") (pinfunction "3Y_6") (pintype "passive"))
    )
    (net (code "46") (name "SPI_CLK_SMALL_B") (class "Default")
      (node (ref "IC30") (pin "8") (pinfunction "4Y_8") (pintype "passive"))
    )
    (net (code "47") (name "SPI_CLK_SMALL_DUAL") (class "Default")
      (node (ref "IC26") (pin "4") (pinfunction "2Y_4") (pintype "passive"))
    )
    (net (code "48") (name "SPI_CLKb_DUAL") (class "Default")
      (node (ref "IC25") (pin "3") (pinfunction "~{E}_3") (pintype "passive"))
    )
    (net (code "49") (name "SPI_CLKb_SINGLE") (class "Default")
      (node (ref "IC40") (pin "3") (pinfunction "~{E}_3") (pintype "passive"))
    )
    (net (code "50") (name "SPI_CSb_DUAL") (class "Default")
      (node (ref "IC27") (pin "3") (pinfunction "~{E}_3") (pintype "passive"))
    )
    (net (code "51") (name "SPI_CSb_MAIN_A") (class "Default")
      (node (ref "IC29") (pin "6") (pinfunction "Y0_6") (pintype "passive"))
    )
    (net (code "52") (name "SPI_CSb_MAIN_B") (class "Default")
      (node (ref "IC29") (pin "4") (pinfunction "Y1_4") (pintype "passive"))
    )
    (net (code "53") (name "SPI_CSb_MAIN_DUAL") (class "Default")
      (node (ref "IC27") (pin "6") (pinfunction "Y0_6") (pintype "passive"))
    )
    (net (code "54") (name "SPI_CSb_SINGLE") (class "Default")
      (node (ref "IC28") (pin "3") (pinfunction "~{E}_3") (pintype "passive"))
    )
    (net (code "55") (name "SPI_CSb_SMALL_A") (class "Default")
      (node (ref "IC31") (pin "6") (pinfunction "Y0_6") (pintype "passive"))
    )
    (net (code "56") (name "SPI_CSb_SMALL_B") (class "Default")
      (node (ref "IC31") (pin "4") (pinfunction "Y1_4") (pintype "passive"))
    )
    (net (code "57") (name "SPI_CSb_SMALL_DUAL") (class "Default")
      (node (ref "IC27") (pin "4") (pinfunction "Y1_4") (pintype "passive"))
    )
    (net (code "58") (name "SPI_DIN") (class "Default")
      (node (ref "R19") (pin "2") (pinfunction "2_2") (pintype "passive"))
      (node (ref "R20") (pin "2") (pinfunction "2_2") (pintype "passive"))
      (node (ref "R21") (pin "2") (pinfunction "2_2") (pintype "passive"))
      (node (ref "R22") (pin "2") (pinfunction "2_2") (pintype "passive"))
      (node (ref "R23") (pin "2") (pinfunction "2_2") (pintype "passive"))
      (node (ref "R24") (pin "2") (pinfunction "2_2") (pintype "passive"))
    )
    (net (code "59") (name "SPI_DIN_MAIN_DUAL") (class "Default")
      (node (ref "R19") (pin "1") (pinfunction "1_1") (pintype "passive"))
    )
    (net (code "60") (name "SPI_DIN_MAIN_SINGLE_A") (class "Default")
      (node (ref "R21") (pin "1") (pinfunction "1_1") (pintype "passive"))
    )
    (net (code "61") (name "SPI_DIN_MAIN_SINGLE_B") (class "Default")
      (node (ref "R22") (pin "1") (pinfunction "1_1") (pintype "passive"))
    )
    (net (code "62") (name "SPI_DIN_SMALL_DUAL") (class "Default")
      (node (ref "R20") (pin "1") (pinfunction "1_1") (pintype "passive"))
    )
    (net (code "63") (name "SPI_DIN_SMALL_SINGLE_A") (class "Default")
      (node (ref "R23") (pin "1") (pinfunction "1_1") (pintype "passive"))
    )
    (net (code "64") (name "SPI_DIN_SMALL_SINGLE_B") (class "Default")
      (node (ref "R24") (pin "1") (pinfunction "1_1") (pintype "passive"))
    )
    (net (code "65") (name "SPI_DOUT_DUAL") (class "Default")
      (node (ref "IC24") (pin "7") (pinfunction "1Y_7") (pintype "passive"))
    )
    (net (code "66") (name "SPI_DOUT_MAIN_A") (class "Default")
      (node (ref "IC22") (pin "10") (pinfunction "2C0_10") (pintype "passive"))
    )
    (net (code "67") (name "SPI_DOUT_MAIN_B") (class "Default")
      (node (ref "IC22") (pin "12") (pinfunction "2C2_12") (pintype "passive"))
    )
    (net (code "68") (name "SPI_DOUT_MAIN_DUAL") (class "Default")
      (node (ref "IC24") (pin "4") (pinfunction "1C2_4") (pintype "passive"))
      (node (ref "IC24") (pin "6") (pinfunction "1C0_6") (pintype "passive"))
    )
    (net (code "69") (name "SPI_DOUT_SINGLE") (class "Default")
      (node (ref "IC22") (pin "9") (pinfunction "2Y_9") (pintype "passive"))
    )
    (net (code "70") (name "SPI_DOUT_SMALL_A") (class "Default")
      (node (ref "IC22") (pin "11") (pinfunction "2C1_11") (pintype "passive"))
    )
    (net (code "71") (name "SPI_DOUT_SMALL_B") (class "Default")
      (node (ref "IC22") (pin "13") (pinfunction "2C3_13") (pintype "passive"))
    )
    (net (code "72") (name "SPI_DOUT_SMALL_DUAL") (class "Default")
      (node (ref "IC24") (pin "3") (pinfunction "1C3_3") (pintype "passive"))
      (node (ref "IC24") (pin "5") (pinfunction "1C1_5") (pintype "passive"))
    )
    (net (code "73") (name "TDC_EN_MAIN_A") (class "Default")
      (node (ref "IC32") (pin "6") (pinfunction "3Y_6") (pintype "passive"))
    )
    (net (code "74") (name "TDC_EN_MAIN_B") (class "Default")
      (node (ref "IC32") (pin "8") (pinfunction "4Y_8") (pintype "passive"))
    )
    (net (code "75") (name "TDC_EN_MAIN_DUAL") (class "Default")
      (node (ref "IC30") (pin "10") (pinfunction "5Y_10") (pintype "passive"))
    )
    (net (code "76") (name "TDC_EN_SMALL_A") (class "Default")
      (node (ref "IC32") (pin "10") (pinfunction "5Y_10") (pintype "passive"))
    )
    (net (code "77") (name "TDC_EN_SMALL_B") (class "Default")
      (node (ref "IC32") (pin "12") (pinfunction "6Y_12") (pintype "passive"))
    )
    (net (code "78") (name "TDC_EN_SMALL_DUAL") (class "Default")
      (node (ref "IC30") (pin "12") (pinfunction "6Y_12") (pintype "passive"))
    )
    (net (code "79") (name "TDC_ENb_DUAL") (class "Default")
      (node (ref "IC44") (pin "3") (pinfunction "~{E}_3") (pintype "passive"))
    )
    (net (code "80") (name "TDC_ENb_SINGLE") (class "Default")
      (node (ref "IC33") (pin "3") (pinfunction "~{E}_3") (pintype "passive"))
    )
    (net (code "81") (name "TDC_INTRb_DUAL") (class "Default")
      (node (ref "IC24") (pin "9") (pinfunction "2Y_9") (pintype "passive"))
    )
    (net (code "82") (name "TDC_INTRb_MAIN_A") (class "Default")
      (node (ref "IC23") (pin "6") (pinfunction "1C0_6") (pintype "passive"))
    )
    (net (code "83") (name "TDC_INTRb_MAIN_B") (class "Default")
      (node (ref "IC23") (pin "4") (pinfunction "1C2_4") (pintype "passive"))
    )
    (net (code "84") (name "TDC_INTRb_MAIN_DUAL") (class "Default")
      (node (ref "IC24") (pin "10") (pinfunction "2C0_10") (pintype "passive"))
      (node (ref "IC24") (pin "12") (pinfunction "2C2_12") (pintype "passive"))
    )
    (net (code "85") (name "TDC_INTRb_SINGLE") (class "Default")
      (node (ref "IC23") (pin "7") (pinfunction "1Y_7") (pintype "passive"))
    )
    (net (code "86") (name "TDC_INTRb_SMALL_A") (class "Default")
      (node (ref "IC23") (pin "5") (pinfunction "1C1_5") (pintype "passive"))
    )
    (net (code "87") (name "TDC_INTRb_SMALL_B") (class "Default")
      (node (ref "IC23") (pin "3") (pinfunction "1C3_3") (pintype "passive"))
    )
    (net (code "88") (name "TDC_INTRb_SMALL_DUAL") (class "Default")
      (node (ref "IC24") (pin "11") (pinfunction "2C1_11") (pintype "passive"))
      (node (ref "IC24") (pin "13") (pinfunction "2C3_13") (pintype "passive"))
    )
    (net (code "89") (name "TDC_TRIGG_DUAL") (class "Default")
      (node (ref "IC23") (pin "9") (pinfunction "2Y_9") (pintype "passive"))
    )
    (net (code "90") (name "TDC_TRIGG_MAIN_A") (class "Default")
      (node (ref "IC22") (pin "6") (pinfunction "1C0_6") (pintype "passive"))
    )
    (net (code "91") (name "TDC_TRIGG_MAIN_B") (class "Default")
      (node (ref "IC22") (pin "4") (pinfunction "1C2_4") (pintype "passive"))
    )
    (net (code "92") (name "TDC_TRIGG_MAIN_DUAL") (class "Default")
      (node (ref "IC23") (pin "10") (pinfunction "2C0_10") (pintype "passive"))
      (node (ref "IC23") (pin "12") (pinfunction "2C2_12") (pintype "passive"))
    )
    (net (code "93") (name "TDC_TRIGG_SINGLE") (class "Default")
      (node (ref "IC22") (pin "7") (pinfunction "1Y_7") (pintype "passive"))
    )
    (net (code "94") (name "TDC_TRIGG_SMALL_A") (class "Default")
      (node (ref "IC22") (pin "5") (pinfunction "1C1_5") (pintype "passive"))
    )
    (net (code "95") (name "TDC_TRIGG_SMALL_B") (class "Default")
      (node (ref "IC22") (pin "3") (pinfunction "1C3_3") (pintype "passive"))
    )
    (net (code "96") (name "TDC_TRIGG_SMALL_DUAL") (class "Default")
      (node (ref "IC23") (pin "11") (pinfunction "2C1_11") (pintype "passive"))
      (node (ref "IC23") (pin "13") (pinfunction "2C3_13") (pintype "passive"))
    )
    (net (code "97") (name "VREF_ATTEN_MAIN_A") (class "Default")
      (node (ref "P48") (pin "1") (pinfunction "1_1") (pintype "passive"))
    )
    (net (code "98") (name "VREF_ATTEN_MAIN_B") (class "Default")
      (node (ref "P48") (pin "2") (pinfunction "2_2") (pintype "passive"))
    )
    (net (code "99") (name "VRST_PK_TEST_A") (class "Default")
      (node (ref "P47") (pin "1") (pinfunction "1_1") (pintype "passive"))
    )
    (net (code "100") (name "VRST_PK_TEST_B") (class "Default")
      (node (ref "P47") (pin "2") (pinfunction "2_2") (pintype "passive"))
    )
    (net (code "101") (name "unconnected-(IC26-3Y-Pad6)") (class "Default")
      (node (ref "IC26") (pin "6") (pinfunction "3Y_6") (pintype "passive"))
    )
    (net (code "102") (name "unconnected-(IC26-4Y-Pad8)") (class "Default")
      (node (ref "IC26") (pin "8") (pinfunction "4Y_8") (pintype "passive"))
    )
    (net (code "103") (name "unconnected-(IC26-5Y-Pad10)") (class "Default")
      (node (ref "IC26") (pin "10") (pinfunction "5Y_10") (pintype "passive"))
    )
    (net (code "104") (name "unconnected-(IC26-6Y-Pad12)") (class "Default")
      (node (ref "IC26") (pin "12") (pinfunction "6Y_12") (pintype "passive"))
    )
    (net (code "105") (name "unconnected-(IC32-1Y-Pad2)") (class "Default")
      (node (ref "IC32") (pin "2") (pinfunction "1Y_2") (pintype "passive"))
    )
    (net (code "106") (name "unconnected-(IC32-2Y-Pad4)") (class "Default")
      (node (ref "IC32") (pin "4") (pinfunction "2Y_4") (pintype "passive"))
    )
    (net (code "107") (name "unconnected-(IC36-3Y-Pad6)") (class "Default")
      (node (ref "IC36") (pin "6") (pinfunction "3Y_6") (pintype "passive"))
    )
    (net (code "108") (name "unconnected-(IC36-4Y-Pad8)") (class "Default")
      (node (ref "IC36") (pin "8") (pinfunction "4Y_8") (pintype "passive"))
    )
    (net (code "109") (name "unconnected-(IC36-5Y-Pad10)") (class "Default")
      (node (ref "IC36") (pin "10") (pinfunction "5Y_10") (pintype "passive"))
    )
    (net (code "110") (name "unconnected-(IC36-6Y-Pad12)") (class "Default")
      (node (ref "IC36") (pin "12") (pinfunction "6Y_12") (pintype "passive"))
    )
    (net (code "111") (name "unconnected-(IC42-2Y-Pad9)") (class "Default")
      (node (ref "IC42") (pin "9") (pinfunction "2Y_9") (pintype "passive"))
    )
  )
)
